# DualPanningMixer.net
KiCad netlist of a schematic drawn in EAGLE
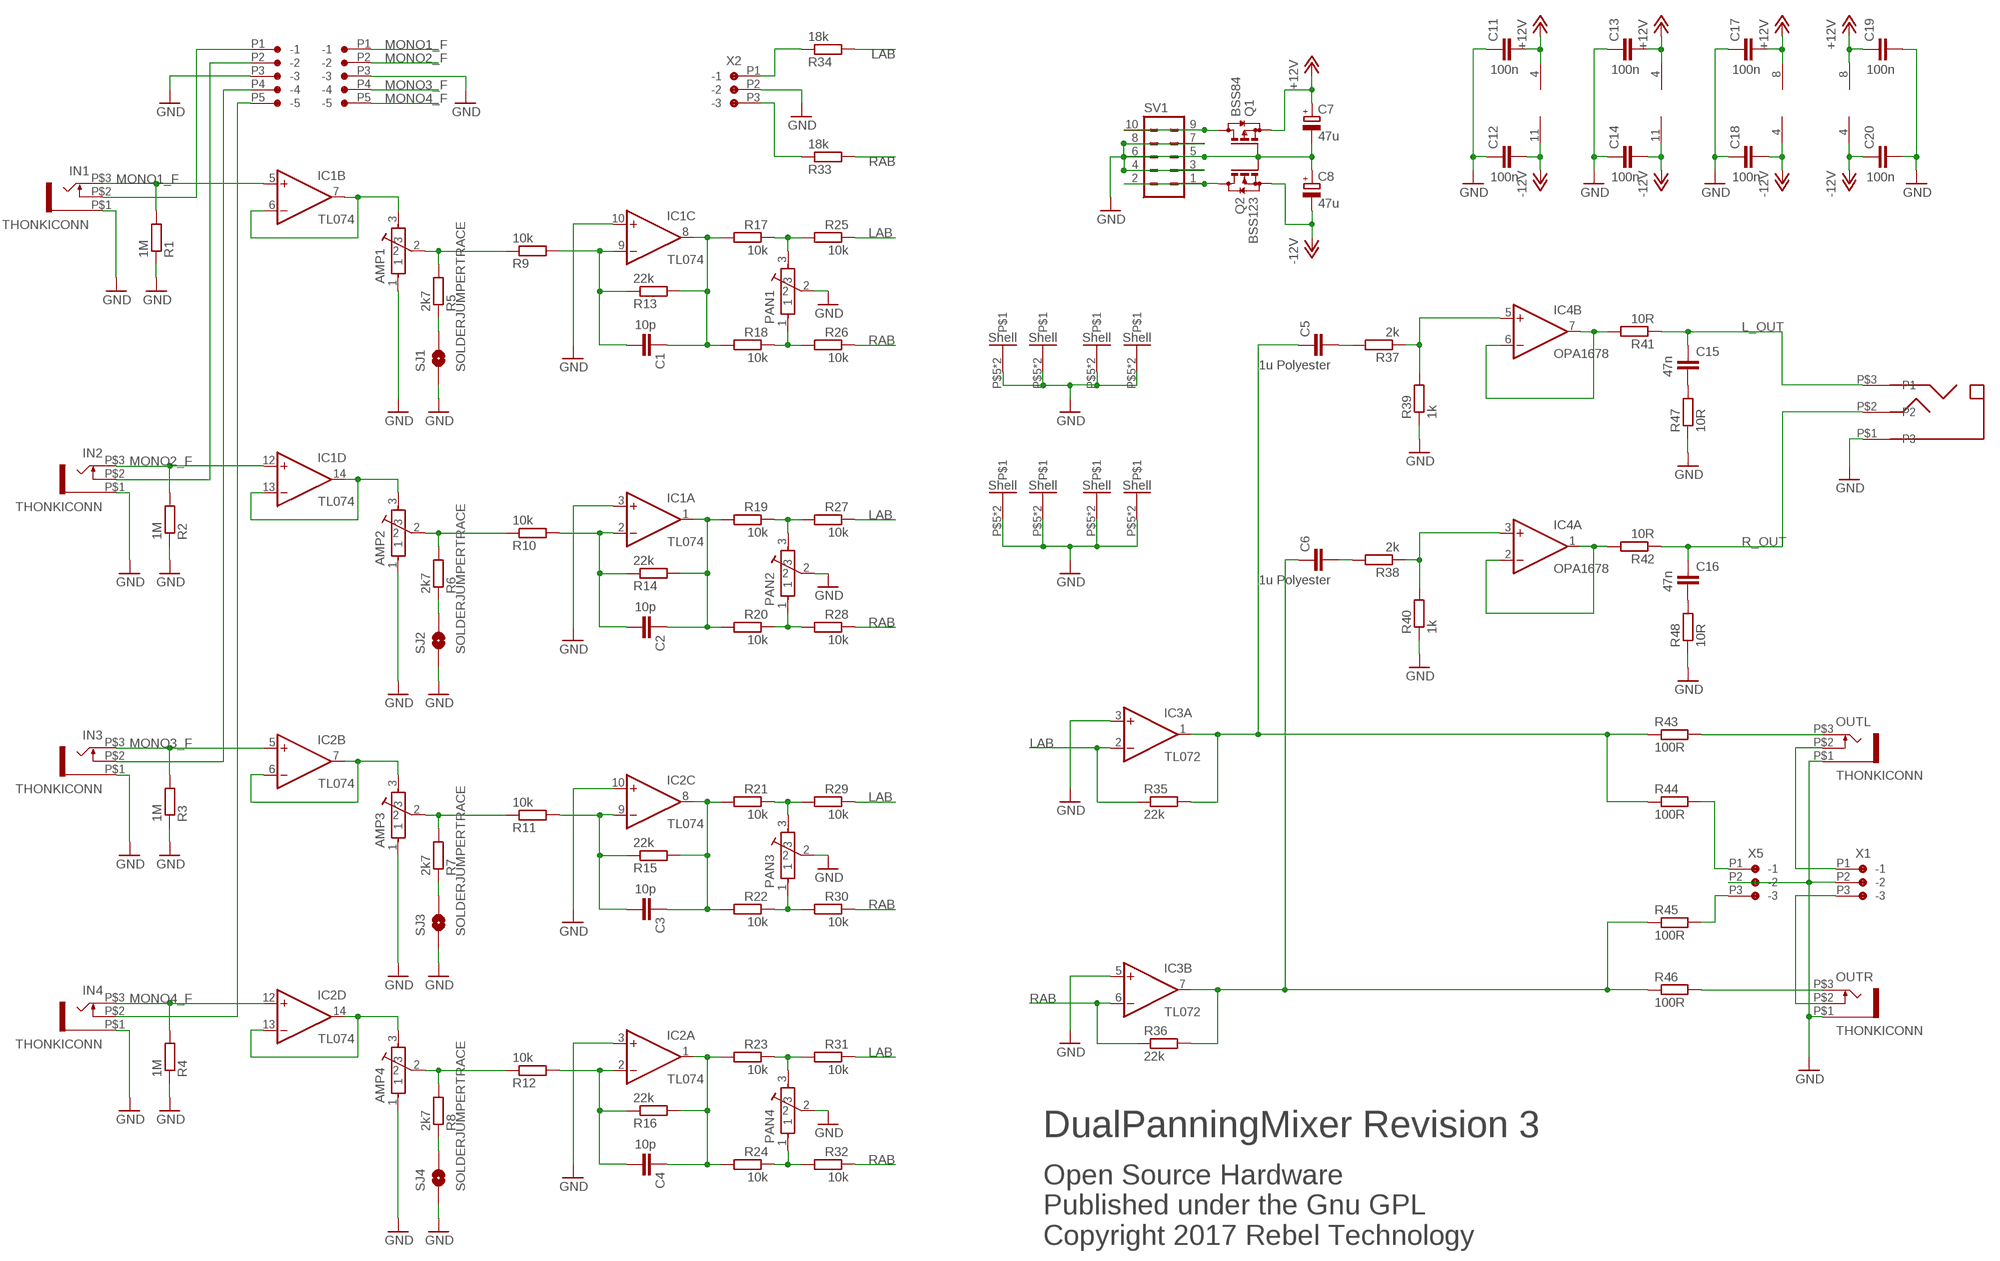
[diagram p0: schematic, sheet 1]

(export (version "E")
  (design (tool "Eeschema 10.0.6"))
  (components
    (comp (ref "AMP1")
      (value "POT-ALPS-RK09L1140")
      (footprint "eagle-import:POT-ALPS-RK09L1140")
      (libsource (lib "eagle-import") (part "POT-ALPS-RK09L1140"))
    )
    (comp (ref "AMP2")
      (value "POT-ALPS-RK09L1140")
      (footprint "eagle-import:POT-ALPS-RK09L1140")
      (libsource (lib "eagle-import") (part "POT-ALPS-RK09L1140"))
    )
    (comp (ref "AMP3")
      (value "POT-ALPS-RK09L1140")
      (footprint "eagle-import:POT-ALPS-RK09L1140")
      (libsource (lib "eagle-import") (part "POT-ALPS-RK09L1140"))
    )
    (comp (ref "AMP4")
      (value "POT-ALPS-RK09L1140")
      (footprint "eagle-import:POT-ALPS-RK09L1140")
      (libsource (lib "eagle-import") (part "POT-ALPS-RK09L1140"))
    )
    (comp (ref "C1")
      (value "10p")
      (footprint "eagle-import:C0603")
      (libsource (lib "eagle-import") (part "C-EUC0603"))
    )
    (comp (ref "C2")
      (value "10p")
      (footprint "eagle-import:C0603")
      (libsource (lib "eagle-import") (part "C-EUC0603"))
    )
    (comp (ref "C3")
      (value "10p")
      (footprint "eagle-import:C0603")
      (libsource (lib "eagle-import") (part "C-EUC0603"))
    )
    (comp (ref "C4")
      (value "10p")
      (footprint "eagle-import:C0603")
      (libsource (lib "eagle-import") (part "C-EUC0603"))
    )
    (comp (ref "C5")
      (value "1u Polyester")
      (footprint "eagle-import:C1210")
      (libsource (lib "eagle-import") (part "C-EUC1210"))
    )
    (comp (ref "C6")
      (value "1u Polyester")
      (footprint "eagle-import:C1210")
      (libsource (lib "eagle-import") (part "C-EUC1210"))
    )
    (comp (ref "C7")
      (value "47u")
      (footprint "eagle-import:UD-5X5,8_NICHICON")
      (libsource (lib "eagle-import") (part "CPOL-EUUD-5X5,8"))
    )
    (comp (ref "C8")
      (value "47u")
      (footprint "eagle-import:UD-5X5,8_NICHICON")
      (libsource (lib "eagle-import") (part "CPOL-EUUD-5X5,8"))
    )
    (comp (ref "C11")
      (value "100n")
      (footprint "eagle-import:C0603")
      (libsource (lib "eagle-import") (part "C-EUC0603"))
    )
    (comp (ref "C12")
      (value "100n")
      (footprint "eagle-import:C0603")
      (libsource (lib "eagle-import") (part "C-EUC0603"))
    )
    (comp (ref "C13")
      (value "100n")
      (footprint "eagle-import:C0603")
      (libsource (lib "eagle-import") (part "C-EUC0603"))
    )
    (comp (ref "C14")
      (value "100n")
      (footprint "eagle-import:C0603")
      (libsource (lib "eagle-import") (part "C-EUC0603"))
    )
    (comp (ref "C15")
      (value "47n")
      (footprint "eagle-import:C0603")
      (libsource (lib "eagle-import") (part "C-EUC0603"))
    )
    (comp (ref "C16")
      (value "47n")
      (footprint "eagle-import:C0603")
      (libsource (lib "eagle-import") (part "C-EUC0603"))
    )
    (comp (ref "C17")
      (value "100n")
      (footprint "eagle-import:C0603")
      (libsource (lib "eagle-import") (part "C-EUC0603"))
    )
    (comp (ref "C18")
      (value "100n")
      (footprint "eagle-import:C0603")
      (libsource (lib "eagle-import") (part "C-EUC0603"))
    )
    (comp (ref "C19")
      (value "100n")
      (footprint "eagle-import:C0603")
      (libsource (lib "eagle-import") (part "C-EUC0603"))
    )
    (comp (ref "C20")
      (value "100n")
      (footprint "eagle-import:C0603")
      (libsource (lib "eagle-import") (part "C-EUC0603"))
    )
    (comp (ref "IC1")
      (value "TL074")
      (footprint "eagle-import:SO14")
      (libsource (lib "eagle-import") (part "TL074D"))
    )
    (comp (ref "IC2")
      (value "TL074")
      (footprint "eagle-import:SO14")
      (libsource (lib "eagle-import") (part "TL074D"))
    )
    (comp (ref "IC3")
      (value "TL072")
      (footprint "eagle-import:SO08")
      (libsource (lib "eagle-import") (part "NE5532D"))
    )
    (comp (ref "IC4")
      (value "OPA1678")
      (footprint "eagle-import:SO08")
      (libsource (lib "eagle-import") (part "NE5532D"))
    )
    (comp (ref "IN1")
      (value "THONKICONN")
      (footprint "eagle-import:THONKICONN")
      (libsource (lib "eagle-import") (part "THONKICONN"))
    )
    (comp (ref "IN2")
      (value "THONKICONN")
      (footprint "eagle-import:THONKICONN")
      (libsource (lib "eagle-import") (part "THONKICONN"))
    )
    (comp (ref "IN3")
      (value "THONKICONN")
      (footprint "eagle-import:THONKICONN")
      (libsource (lib "eagle-import") (part "THONKICONN"))
    )
    (comp (ref "IN4")
      (value "THONKICONN")
      (footprint "eagle-import:THONKICONN")
      (libsource (lib "eagle-import") (part "THONKICONN"))
    )
    (comp (ref "OUTHP")
      (value "THONKICONN_STEREO")
      (footprint "eagle-import:THONKICONN_STEREO")
      (libsource (lib "eagle-import") (part "THONKICONN_STEREO"))
    )
    (comp (ref "OUTL")
      (value "THONKICONN")
      (footprint "eagle-import:THONKICONN")
      (libsource (lib "eagle-import") (part "THONKICONN"))
    )
    (comp (ref "OUTR")
      (value "THONKICONN")
      (footprint "eagle-import:THONKICONN")
      (libsource (lib "eagle-import") (part "THONKICONN"))
    )
    (comp (ref "PAN1")
      (value "POT-ALPS-RK09L1140")
      (footprint "eagle-import:POT-ALPS-RK09L1140")
      (libsource (lib "eagle-import") (part "POT-ALPS-RK09L1140"))
    )
    (comp (ref "PAN2")
      (value "POT-ALPS-RK09L1140")
      (footprint "eagle-import:POT-ALPS-RK09L1140")
      (libsource (lib "eagle-import") (part "POT-ALPS-RK09L1140"))
    )
    (comp (ref "PAN3")
      (value "POT-ALPS-RK09L1140")
      (footprint "eagle-import:POT-ALPS-RK09L1140")
      (libsource (lib "eagle-import") (part "POT-ALPS-RK09L1140"))
    )
    (comp (ref "PAN4")
      (value "POT-ALPS-RK09L1140")
      (footprint "eagle-import:POT-ALPS-RK09L1140")
      (libsource (lib "eagle-import") (part "POT-ALPS-RK09L1140"))
    )
    (comp (ref "Q1")
      (value "BSS84")
      (footprint "eagle-import:SOT23")
      (libsource (lib "eagle-import") (part "BSS84"))
    )
    (comp (ref "Q2")
      (value "BSS123")
      (footprint "eagle-import:SOT23")
      (libsource (lib "eagle-import") (part "BSS123"))
    )
    (comp (ref "R1")
      (value "1M")
      (footprint "eagle-import:0603")
      (libsource (lib "eagle-import") (part "R-EU_0603"))
    )
    (comp (ref "R2")
      (value "1M")
      (footprint "eagle-import:0603")
      (libsource (lib "eagle-import") (part "R-EU_0603"))
    )
    (comp (ref "R3")
      (value "1M")
      (footprint "eagle-import:0603")
      (libsource (lib "eagle-import") (part "R-EU_0603"))
    )
    (comp (ref "R4")
      (value "1M")
      (footprint "eagle-import:0603")
      (libsource (lib "eagle-import") (part "R-EU_0603"))
    )
    (comp (ref "R5")
      (value "2k7")
      (footprint "eagle-import:0603")
      (libsource (lib "eagle-import") (part "R-EU_0603"))
    )
    (comp (ref "R6")
      (value "2k7")
      (footprint "eagle-import:0603")
      (libsource (lib "eagle-import") (part "R-EU_0603"))
    )
    (comp (ref "R7")
      (value "2k7")
      (footprint "eagle-import:0603")
      (libsource (lib "eagle-import") (part "R-EU_0603"))
    )
    (comp (ref "R8")
      (value "2k7")
      (footprint "eagle-import:0603")
      (libsource (lib "eagle-import") (part "R-EU_0603"))
    )
    (comp (ref "R9")
      (value "10k")
      (footprint "eagle-import:0603")
      (libsource (lib "eagle-import") (part "R-EU_0603"))
    )
    (comp (ref "R10")
      (value "10k")
      (footprint "eagle-import:0603")
      (libsource (lib "eagle-import") (part "R-EU_0603"))
    )
    (comp (ref "R11")
      (value "10k")
      (footprint "eagle-import:0603")
      (libsource (lib "eagle-import") (part "R-EU_0603"))
    )
    (comp (ref "R12")
      (value "10k")
      (footprint "eagle-import:0603")
      (libsource (lib "eagle-import") (part "R-EU_0603"))
    )
    (comp (ref "R13")
      (value "22k")
      (footprint "eagle-import:0603")
      (libsource (lib "eagle-import") (part "R-EU_0603"))
    )
    (comp (ref "R14")
      (value "22k")
      (footprint "eagle-import:0603")
      (libsource (lib "eagle-import") (part "R-EU_0603"))
    )
    (comp (ref "R15")
      (value "22k")
      (footprint "eagle-import:0603")
      (libsource (lib "eagle-import") (part "R-EU_0603"))
    )
    (comp (ref "R16")
      (value "22k")
      (footprint "eagle-import:0603")
      (libsource (lib "eagle-import") (part "R-EU_0603"))
    )
    (comp (ref "R17")
      (value "10k")
      (footprint "eagle-import:0603")
      (libsource (lib "eagle-import") (part "R-EU_0603"))
    )
    (comp (ref "R18")
      (value "10k")
      (footprint "eagle-import:0603")
      (libsource (lib "eagle-import") (part "R-EU_0603"))
    )
    (comp (ref "R19")
      (value "10k")
      (footprint "eagle-import:0603")
      (libsource (lib "eagle-import") (part "R-EU_0603"))
    )
    (comp (ref "R20")
      (value "10k")
      (footprint "eagle-import:0603")
      (libsource (lib "eagle-import") (part "R-EU_0603"))
    )
    (comp (ref "R21")
      (value "10k")
      (footprint "eagle-import:0603")
      (libsource (lib "eagle-import") (part "R-EU_0603"))
    )
    (comp (ref "R22")
      (value "10k")
      (footprint "eagle-import:0603")
      (libsource (lib "eagle-import") (part "R-EU_0603"))
    )
    (comp (ref "R23")
      (value "10k")
      (footprint "eagle-import:0603")
      (libsource (lib "eagle-import") (part "R-EU_0603"))
    )
    (comp (ref "R24")
      (value "10k")
      (footprint "eagle-import:0603")
      (libsource (lib "eagle-import") (part "R-EU_0603"))
    )
    (comp (ref "R25")
      (value "10k")
      (footprint "eagle-import:0603")
      (libsource (lib "eagle-import") (part "R-EU_0603"))
    )
    (comp (ref "R26")
      (value "10k")
      (footprint "eagle-import:0603")
      (libsource (lib "eagle-import") (part "R-EU_0603"))
    )
    (comp (ref "R27")
      (value "10k")
      (footprint "eagle-import:0603")
      (libsource (lib "eagle-import") (part "R-EU_0603"))
    )
    (comp (ref "R28")
      (value "10k")
      (footprint "eagle-import:0603")
      (libsource (lib "eagle-import") (part "R-EU_0603"))
    )
    (comp (ref "R29")
      (value "10k")
      (footprint "eagle-import:0603")
      (libsource (lib "eagle-import") (part "R-EU_0603"))
    )
    (comp (ref "R30")
      (value "10k")
      (footprint "eagle-import:0603")
      (libsource (lib "eagle-import") (part "R-EU_0603"))
    )
    (comp (ref "R31")
      (value "10k")
      (footprint "eagle-import:0603")
      (libsource (lib "eagle-import") (part "R-EU_0603"))
    )
    (comp (ref "R32")
      (value "10k")
      (footprint "eagle-import:0603")
      (libsource (lib "eagle-import") (part "R-EU_0603"))
    )
    (comp (ref "R33")
      (value "18k")
      (footprint "eagle-import:0603")
      (libsource (lib "eagle-import") (part "R-EU_0603"))
    )
    (comp (ref "R34")
      (value "18k")
      (footprint "eagle-import:0603")
      (libsource (lib "eagle-import") (part "R-EU_0603"))
    )
    (comp (ref "R35")
      (value "22k")
      (footprint "eagle-import:0603")
      (libsource (lib "eagle-import") (part "R-EU_0603"))
    )
    (comp (ref "R36")
      (value "22k")
      (footprint "eagle-import:0603")
      (libsource (lib "eagle-import") (part "R-EU_0603"))
    )
    (comp (ref "R37")
      (value "2k")
      (footprint "eagle-import:0603")
      (libsource (lib "eagle-import") (part "R-EU_0603"))
    )
    (comp (ref "R38")
      (value "2k")
      (footprint "eagle-import:0603")
      (libsource (lib "eagle-import") (part "R-EU_0603"))
    )
    (comp (ref "R39")
      (value "1k")
      (footprint "eagle-import:0603")
      (libsource (lib "eagle-import") (part "R-EU_0603"))
    )
    (comp (ref "R40")
      (value "1k")
      (footprint "eagle-import:0603")
      (libsource (lib "eagle-import") (part "R-EU_0603"))
    )
    (comp (ref "R41")
      (value "10R")
      (footprint "eagle-import:0603")
      (libsource (lib "eagle-import") (part "R-EU_0603"))
    )
    (comp (ref "R42")
      (value "10R")
      (footprint "eagle-import:0603")
      (libsource (lib "eagle-import") (part "R-EU_0603"))
    )
    (comp (ref "R43")
      (value "100R")
      (footprint "eagle-import:0603")
      (libsource (lib "eagle-import") (part "R-EU_0603"))
    )
    (comp (ref "R44")
      (value "100R")
      (footprint "eagle-import:0603")
      (libsource (lib "eagle-import") (part "R-EU_0603"))
    )
    (comp (ref "R45")
      (value "100R")
      (footprint "eagle-import:0603")
      (libsource (lib "eagle-import") (part "R-EU_0603"))
    )
    (comp (ref "R46")
      (value "100R")
      (footprint "eagle-import:0603")
      (libsource (lib "eagle-import") (part "R-EU_0603"))
    )
    (comp (ref "R47")
      (value "10R")
      (footprint "eagle-import:0603")
      (libsource (lib "eagle-import") (part "R-EU_0603"))
    )
    (comp (ref "R48")
      (value "10R")
      (footprint "eagle-import:0603")
      (libsource (lib "eagle-import") (part "R-EU_0603"))
    )
    (comp (ref "SJ1")
      (value "SOLDERJUMPERTRACE")
      (footprint "eagle-import:SJ_2S-TRACE")
      (libsource (lib "eagle-import") (part "SOLDERJUMPERTRACE"))
    )
    (comp (ref "SJ2")
      (value "SOLDERJUMPERTRACE")
      (footprint "eagle-import:SJ_2S-TRACE")
      (libsource (lib "eagle-import") (part "SOLDERJUMPERTRACE"))
    )
    (comp (ref "SJ3")
      (value "SOLDERJUMPERTRACE")
      (footprint "eagle-import:SJ_2S-TRACE")
      (libsource (lib "eagle-import") (part "SOLDERJUMPERTRACE"))
    )
    (comp (ref "SJ4")
      (value "SOLDERJUMPERTRACE")
      (footprint "eagle-import:SJ_2S-TRACE")
      (libsource (lib "eagle-import") (part "SOLDERJUMPERTRACE"))
    )
    (comp (ref "SV1")
      (value "MA05-2")
      (footprint "eagle-import:MA05-2")
      (libsource (lib "eagle-import") (part "MA05-2"))
    )
    (comp (ref "X1")
      (value "CON-JST_PH_3W")
      (footprint "eagle-import:CON-JST_PH_3W")
      (libsource (lib "eagle-import") (part "CON-JST_PH_3W"))
    )
    (comp (ref "X2")
      (value "CON-JST_PH_3W")
      (footprint "eagle-import:CON-JST_PH_3W")
      (libsource (lib "eagle-import") (part "CON-JST_PH_3W"))
    )
    (comp (ref "X3")
      (value "CON-JST_PH_5W")
      (footprint "eagle-import:CON-JST_PH_5W")
      (libsource (lib "eagle-import") (part "CON-JST_PH_5W"))
    )
    (comp (ref "X4")
      (value "CON-JST_PH_5W")
      (footprint "eagle-import:CON-JST_PH_5W")
      (libsource (lib "eagle-import") (part "CON-JST_PH_5W"))
    )
    (comp (ref "X5")
      (value "CON-JST_PH_3W")
      (footprint "eagle-import:CON-JST_PH_3W")
      (libsource (lib "eagle-import") (part "CON-JST_PH_3W"))
    )
  )
  (nets
    (net (code "1") (name "+12V") (class "Default")
      (node (ref "C11") (pin "2") (pinfunction "2_2") (pintype "passive"))
      (node (ref "C13") (pin "2") (pinfunction "2_2") (pintype "passive"))
      (node (ref "C17") (pin "2") (pinfunction "2_2") (pintype "passive"))
      (node (ref "C19") (pin "1") (pinfunction "1_1") (pintype "passive"))
      (node (ref "C7") (pin "+") (pinfunction "+_+") (pintype "passive"))
      (node (ref "IC1") (pin "4") (pinfunction "V+_4") (pintype "power_in"))
      (node (ref "IC2") (pin "4") (pinfunction "V+_4") (pintype "power_in"))
      (node (ref "IC3") (pin "8") (pinfunction "V+_8") (pintype "power_in"))
      (node (ref "IC4") (pin "8") (pinfunction "V+_8") (pintype "power_in"))
      (node (ref "Q1") (pin "2") (pinfunction "S_2") (pintype "passive"))
    )
    (net (code "2") (name "-12V") (class "Default")
      (node (ref "C12") (pin "2") (pinfunction "2_2") (pintype "passive"))
      (node (ref "C14") (pin "2") (pinfunction "2_2") (pintype "passive"))
      (node (ref "C18") (pin "2") (pinfunction "2_2") (pintype "passive"))
      (node (ref "C20") (pin "1") (pinfunction "1_1") (pintype "passive"))
      (node (ref "C8") (pin "-") (pinfunction "-_-") (pintype "passive"))
      (node (ref "IC1") (pin "11") (pinfunction "V-_11") (pintype "power_in"))
      (node (ref "IC2") (pin "11") (pinfunction "V-_11") (pintype "power_in"))
      (node (ref "IC3") (pin "4") (pinfunction "V-_4") (pintype "power_in"))
      (node (ref "IC4") (pin "4") (pinfunction "V-_4") (pintype "power_in"))
      (node (ref "Q2") (pin "2") (pinfunction "S_2") (pintype "passive"))
    )
    (net (code "3") (name "/LAB") (class "Default")
      (node (ref "IC3") (pin "2") (pinfunction "-IN_2") (pintype "input"))
      (node (ref "R25") (pin "1") (pinfunction "1_1") (pintype "passive"))
      (node (ref "R27") (pin "1") (pinfunction "1_1") (pintype "passive"))
      (node (ref "R29") (pin "1") (pinfunction "1_1") (pintype "passive"))
      (node (ref "R31") (pin "1") (pinfunction "1_1") (pintype "passive"))
      (node (ref "R34") (pin "2") (pinfunction "2_2") (pintype "passive"))
      (node (ref "R35") (pin "1") (pinfunction "1_1") (pintype "passive"))
    )
    (net (code "4") (name "/L_OUT") (class "Default")
      (node (ref "C15") (pin "1") (pinfunction "1_1") (pintype "passive"))
      (node (ref "OUTHP") (pin "P$3") (pinfunction "P1_P$3") (pintype "bidirectional"))
      (node (ref "R41") (pin "1") (pinfunction "1_1") (pintype "passive"))
    )
    (net (code "5") (name "/MONO1_F") (class "Default")
      (node (ref "IC1") (pin "5") (pinfunction "+IN_5") (pintype "input"))
      (node (ref "IN1") (pin "P$3") (pinfunction "3_P$3") (pintype "passive"))
      (node (ref "R1") (pin "2") (pinfunction "2_2") (pintype "passive"))
      (node (ref "X3") (pin "P1") (pinfunction "-1_P1") (pintype "bidirectional"))
    )
    (net (code "6") (name "/MONO2_F") (class "Default")
      (node (ref "IC1") (pin "12") (pinfunction "+IN_12") (pintype "input"))
      (node (ref "IN2") (pin "P$3") (pinfunction "3_P$3") (pintype "passive"))
      (node (ref "R2") (pin "2") (pinfunction "2_2") (pintype "passive"))
      (node (ref "X3") (pin "P2") (pinfunction "-2_P2") (pintype "bidirectional"))
    )
    (net (code "7") (name "/MONO3_F") (class "Default")
      (node (ref "IC2") (pin "5") (pinfunction "+IN_5") (pintype "input"))
      (node (ref "IN3") (pin "P$3") (pinfunction "3_P$3") (pintype "passive"))
      (node (ref "R3") (pin "2") (pinfunction "2_2") (pintype "passive"))
      (node (ref "X3") (pin "P4") (pinfunction "-4_P4") (pintype "bidirectional"))
    )
    (net (code "8") (name "/MONO4_F") (class "Default")
      (node (ref "IC2") (pin "12") (pinfunction "+IN_12") (pintype "input"))
      (node (ref "IN4") (pin "P$3") (pinfunction "3_P$3") (pintype "passive"))
      (node (ref "R4") (pin "2") (pinfunction "2_2") (pintype "passive"))
      (node (ref "X3") (pin "P5") (pinfunction "-5_P5") (pintype "bidirectional"))
    )
    (net (code "9") (name "/RAB") (class "Default")
      (node (ref "IC3") (pin "6") (pinfunction "-IN_6") (pintype "input"))
      (node (ref "R26") (pin "1") (pinfunction "1_1") (pintype "passive"))
      (node (ref "R28") (pin "1") (pinfunction "1_1") (pintype "passive"))
      (node (ref "R30") (pin "1") (pinfunction "1_1") (pintype "passive"))
      (node (ref "R32") (pin "1") (pinfunction "1_1") (pintype "passive"))
      (node (ref "R33") (pin "2") (pinfunction "2_2") (pintype "passive"))
      (node (ref "R36") (pin "1") (pinfunction "1_1") (pintype "passive"))
    )
    (net (code "10") (name "/R_OUT") (class "Default")
      (node (ref "C16") (pin "1") (pinfunction "1_1") (pintype "passive"))
      (node (ref "OUTHP") (pin "P$2") (pinfunction "P2_P$2") (pintype "bidirectional"))
      (node (ref "R42") (pin "1") (pinfunction "1_1") (pintype "passive"))
    )
    (net (code "11") (name "GND") (class "Default")
      (node (ref "AMP1") (pin "1") (pinfunction "1_1") (pintype "bidirectional"))
      (node (ref "AMP1") (pin "P$5") (pinfunction "P$1_P$5") (pintype "bidirectional"))
      (node (ref "AMP1") (pin "P$6") (pinfunction "P$1_P$6") (pintype "bidirectional"))
      (node (ref "AMP2") (pin "1") (pinfunction "1_1") (pintype "bidirectional"))
      (node (ref "AMP2") (pin "P$5") (pinfunction "P$1_P$5") (pintype "bidirectional"))
      (node (ref "AMP2") (pin "P$6") (pinfunction "P$1_P$6") (pintype "bidirectional"))
      (node (ref "AMP3") (pin "1") (pinfunction "1_1") (pintype "bidirectional"))
      (node (ref "AMP3") (pin "P$5") (pinfunction "P$1_P$5") (pintype "bidirectional"))
      (node (ref "AMP3") (pin "P$6") (pinfunction "P$1_P$6") (pintype "bidirectional"))
      (node (ref "AMP4") (pin "1") (pinfunction "1_1") (pintype "bidirectional"))
      (node (ref "AMP4") (pin "P$5") (pinfunction "P$1_P$5") (pintype "bidirectional"))
      (node (ref "AMP4") (pin "P$6") (pinfunction "P$1_P$6") (pintype "bidirectional"))
      (node (ref "C11") (pin "1") (pinfunction "1_1") (pintype "passive"))
      (node (ref "C12") (pin "1") (pinfunction "1_1") (pintype "passive"))
      (node (ref "C13") (pin "1") (pinfunction "1_1") (pintype "passive"))
      (node (ref "C14") (pin "1") (pinfunction "1_1") (pintype "passive"))
      (node (ref "C17") (pin "1") (pinfunction "1_1") (pintype "passive"))
      (node (ref "C18") (pin "1") (pinfunction "1_1") (pintype "passive"))
      (node (ref "C19") (pin "2") (pinfunction "2_2") (pintype "passive"))
      (node (ref "C20") (pin "2") (pinfunction "2_2") (pintype "passive"))
      (node (ref "C7") (pin "-") (pinfunction "-_-") (pintype "passive"))
      (node (ref "C8") (pin "+") (pinfunction "+_+") (pintype "passive"))
      (node (ref "IC1") (pin "10") (pinfunction "+IN_10") (pintype "input"))
      (node (ref "IC1") (pin "3") (pinfunction "+IN_3") (pintype "input"))
      (node (ref "IC2") (pin "10") (pinfunction "+IN_10") (pintype "input"))
      (node (ref "IC2") (pin "3") (pinfunction "+IN_3") (pintype "input"))
      (node (ref "IC3") (pin "3") (pinfunction "+IN_3") (pintype "input"))
      (node (ref "IC3") (pin "5") (pinfunction "+IN_5") (pintype "input"))
      (node (ref "IN1") (pin "P$1") (pinfunction "5_P$1") (pintype "passive"))
      (node (ref "IN2") (pin "P$1") (pinfunction "5_P$1") (pintype "passive"))
      (node (ref "IN3") (pin "P$1") (pinfunction "5_P$1") (pintype "passive"))
      (node (ref "IN4") (pin "P$1") (pinfunction "5_P$1") (pintype "passive"))
      (node (ref "OUTHP") (pin "P$1") (pinfunction "P3_P$1") (pintype "bidirectional"))
      (node (ref "OUTL") (pin "P$1") (pinfunction "5_P$1") (pintype "passive"))
      (node (ref "OUTR") (pin "P$1") (pinfunction "5_P$1") (pintype "passive"))
      (node (ref "PAN1") (pin "2") (pinfunction "2_2") (pintype "bidirectional"))
      (node (ref "PAN1") (pin "P$5") (pinfunction "P$1_P$5") (pintype "bidirectional"))
      (node (ref "PAN1") (pin "P$6") (pinfunction "P$1_P$6") (pintype "bidirectional"))
      (node (ref "PAN2") (pin "2") (pinfunction "2_2") (pintype "bidirectional"))
      (node (ref "PAN2") (pin "P$5") (pinfunction "P$1_P$5") (pintype "bidirectional"))
      (node (ref "PAN2") (pin "P$6") (pinfunction "P$1_P$6") (pintype "bidirectional"))
      (node (ref "PAN3") (pin "2") (pinfunction "2_2") (pintype "bidirectional"))
      (node (ref "PAN3") (pin "P$5") (pinfunction "P$1_P$5") (pintype "bidirectional"))
      (node (ref "PAN3") (pin "P$6") (pinfunction "P$1_P$6") (pintype "bidirectional"))
      (node (ref "PAN4") (pin "2") (pinfunction "2_2") (pintype "bidirectional"))
      (node (ref "PAN4") (pin "P$5") (pinfunction "P$1_P$5") (pintype "bidirectional"))
      (node (ref "PAN4") (pin "P$6") (pinfunction "P$1_P$6") (pintype "bidirectional"))
      (node (ref "Q1") (pin "1") (pinfunction "G_1") (pintype "passive"))
      (node (ref "Q2") (pin "1") (pinfunction "G_1") (pintype "passive"))
      (node (ref "R1") (pin "1") (pinfunction "1_1") (pintype "passive"))
      (node (ref "R2") (pin "1") (pinfunction "1_1") (pintype "passive"))
      (node (ref "R3") (pin "1") (pinfunction "1_1") (pintype "passive"))
      (node (ref "R39") (pin "1") (pinfunction "1_1") (pintype "passive"))
      (node (ref "R4") (pin "1") (pinfunction "1_1") (pintype "passive"))
      (node (ref "R40") (pin "1") (pinfunction "1_1") (pintype "passive"))
      (node (ref "R47") (pin "1") (pinfunction "1_1") (pintype "passive"))
      (node (ref "R48") (pin "1") (pinfunction "1_1") (pintype "passive"))
      (node (ref "SJ1") (pin "1") (pinfunction "1_1") (pintype "passive"))
      (node (ref "SJ2") (pin "1") (pinfunction "1_1") (pintype "passive"))
      (node (ref "SJ3") (pin "1") (pinfunction "1_1") (pintype "passive"))
      (node (ref "SJ4") (pin "1") (pinfunction "1_1") (pintype "passive"))
      (node (ref "SV1") (pin "3") (pinfunction "3_3") (pintype "passive"))
      (node (ref "SV1") (pin "4") (pinfunction "4_4") (pintype "passive"))
      (node (ref "SV1") (pin "5") (pinfunction "5_5") (pintype "passive"))
      (node (ref "SV1") (pin "6") (pinfunction "6_6") (pintype "passive"))
      (node (ref "SV1") (pin "7") (pinfunction "7_7") (pintype "passive"))
      (node (ref "SV1") (pin "8") (pinfunction "8_8") (pintype "passive"))
      (node (ref "X1") (pin "P2") (pinfunction "-2_P2") (pintype "bidirectional"))
      (node (ref "X2") (pin "P2") (pinfunction "-2_P2") (pintype "bidirectional"))
      (node (ref "X3") (pin "P3") (pinfunction "-3_P3") (pintype "bidirectional"))
      (node (ref "X4") (pin "P3") (pinfunction "-3_P3") (pintype "bidirectional"))
      (node (ref "X5") (pin "P2") (pinfunction "-2_P2") (pintype "bidirectional"))
    )
    (net (code "12") (name "Net-(AMP1-Pad2)") (class "Default")
      (node (ref "AMP1") (pin "2") (pinfunction "2_2") (pintype "bidirectional"))
      (node (ref "R5") (pin "2") (pinfunction "2_2") (pintype "passive"))
      (node (ref "R9") (pin "1") (pinfunction "1_1") (pintype "passive"))
    )
    (net (code "13") (name "Net-(AMP2-Pad2)") (class "Default")
      (node (ref "AMP2") (pin "2") (pinfunction "2_2") (pintype "bidirectional"))
      (node (ref "R10") (pin "1") (pinfunction "1_1") (pintype "passive"))
      (node (ref "R6") (pin "2") (pinfunction "2_2") (pintype "passive"))
    )
    (net (code "14") (name "Net-(AMP3-Pad2)") (class "Default")
      (node (ref "AMP3") (pin "2") (pinfunction "2_2") (pintype "bidirectional"))
      (node (ref "R11") (pin "1") (pinfunction "1_1") (pintype "passive"))
      (node (ref "R7") (pin "2") (pinfunction "2_2") (pintype "passive"))
    )
    (net (code "15") (name "Net-(AMP4-Pad2)") (class "Default")
      (node (ref "AMP4") (pin "2") (pinfunction "2_2") (pintype "bidirectional"))
      (node (ref "R12") (pin "1") (pinfunction "1_1") (pintype "passive"))
      (node (ref "R8") (pin "2") (pinfunction "2_2") (pintype "passive"))
    )
    (net (code "16") (name "Net-(C5-Pad2)") (class "Default")
      (node (ref "C5") (pin "2") (pinfunction "2_2") (pintype "passive"))
      (node (ref "R37") (pin "2") (pinfunction "2_2") (pintype "passive"))
    )
    (net (code "17") (name "Net-(C6-Pad2)") (class "Default")
      (node (ref "C6") (pin "2") (pinfunction "2_2") (pintype "passive"))
      (node (ref "R38") (pin "2") (pinfunction "2_2") (pintype "passive"))
    )
    (net (code "18") (name "Net-(C15-Pad2)") (class "Default")
      (node (ref "C15") (pin "2") (pinfunction "2_2") (pintype "passive"))
      (node (ref "R47") (pin "2") (pinfunction "2_2") (pintype "passive"))
    )
    (net (code "19") (name "Net-(C16-Pad2)") (class "Default")
      (node (ref "C16") (pin "2") (pinfunction "2_2") (pintype "passive"))
      (node (ref "R48") (pin "2") (pinfunction "2_2") (pintype "passive"))
    )
    (net (code "20") (name "Net-(IC1A--IN)") (class "Default")
      (node (ref "C2") (pin "2") (pinfunction "2_2") (pintype "passive"))
      (node (ref "IC1") (pin "2") (pinfunction "-IN_2") (pintype "input"))
      (node (ref "R10") (pin "2") (pinfunction "2_2") (pintype "passive"))
      (node (ref "R14") (pin "1") (pinfunction "1_1") (pintype "passive"))
    )
    (net (code "21") (name "Net-(IC1A-OUT)") (class "Default")
      (node (ref "C2") (pin "1") (pinfunction "1_1") (pintype "passive"))
      (node (ref "IC1") (pin "1") (pinfunction "OUT_1") (pintype "output"))
      (node (ref "R14") (pin "2") (pinfunction "2_2") (pintype "passive"))
      (node (ref "R19") (pin "2") (pinfunction "2_2") (pintype "passive"))
      (node (ref "R20") (pin "2") (pinfunction "2_2") (pintype "passive"))
    )
    (net (code "22") (name "Net-(IC1B--IN)") (class "Default")
      (node (ref "AMP1") (pin "3") (pinfunction "3_3") (pintype "bidirectional"))
      (node (ref "IC1") (pin "6") (pinfunction "-IN_6") (pintype "input"))
      (node (ref "IC1") (pin "7") (pinfunction "OUT_7") (pintype "output"))
    )
    (net (code "23") (name "Net-(IC1C--IN)") (class "Default")
      (node (ref "C1") (pin "2") (pinfunction "2_2") (pintype "passive"))
      (node (ref "IC1") (pin "9") (pinfunction "-IN_9") (pintype "input"))
      (node (ref "R13") (pin "1") (pinfunction "1_1") (pintype "passive"))
      (node (ref "R9") (pin "2") (pinfunction "2_2") (pintype "passive"))
    )
    (net (code "24") (name "Net-(IC1C-OUT)") (class "Default")
      (node (ref "C1") (pin "1") (pinfunction "1_1") (pintype "passive"))
      (node (ref "IC1") (pin "8") (pinfunction "OUT_8") (pintype "output"))
      (node (ref "R13") (pin "2") (pinfunction "2_2") (pintype "passive"))
      (node (ref "R17") (pin "2") (pinfunction "2_2") (pintype "passive"))
      (node (ref "R18") (pin "2") (pinfunction "2_2") (pintype "passive"))
    )
    (net (code "25") (name "Net-(IC1D--IN)") (class "Default")
      (node (ref "AMP2") (pin "3") (pinfunction "3_3") (pintype "bidirectional"))
      (node (ref "IC1") (pin "13") (pinfunction "-IN_13") (pintype "input"))
      (node (ref "IC1") (pin "14") (pinfunction "OUT_14") (pintype "output"))
    )
    (net (code "26") (name "Net-(IC2A--IN)") (class "Default")
      (node (ref "C4") (pin "2") (pinfunction "2_2") (pintype "passive"))
      (node (ref "IC2") (pin "2") (pinfunction "-IN_2") (pintype "input"))
      (node (ref "R12") (pin "2") (pinfunction "2_2") (pintype "passive"))
      (node (ref "R16") (pin "1") (pinfunction "1_1") (pintype "passive"))
    )
    (net (code "27") (name "Net-(IC2A-OUT)") (class "Default")
      (node (ref "C4") (pin "1") (pinfunction "1_1") (pintype "passive"))
      (node (ref "IC2") (pin "1") (pinfunction "OUT_1") (pintype "output"))
      (node (ref "R16") (pin "2") (pinfunction "2_2") (pintype "passive"))
      (node (ref "R23") (pin "2") (pinfunction "2_2") (pintype "passive"))
      (node (ref "R24") (pin "2") (pinfunction "2_2") (pintype "passive"))
    )
    (net (code "28") (name "Net-(IC2B--IN)") (class "Default")
      (node (ref "AMP3") (pin "3") (pinfunction "3_3") (pintype "bidirectional"))
      (node (ref "IC2") (pin "6") (pinfunction "-IN_6") (pintype "input"))
      (node (ref "IC2") (pin "7") (pinfunction "OUT_7") (pintype "output"))
    )
    (net (code "29") (name "Net-(IC2C--IN)") (class "Default")
      (node (ref "C3") (pin "2") (pinfunction "2_2") (pintype "passive"))
      (node (ref "IC2") (pin "9") (pinfunction "-IN_9") (pintype "input"))
      (node (ref "R11") (pin "2") (pinfunction "2_2") (pintype "passive"))
      (node (ref "R15") (pin "1") (pinfunction "1_1") (pintype "passive"))
    )
    (net (code "30") (name "Net-(IC2C-OUT)") (class "Default")
      (node (ref "C3") (pin "1") (pinfunction "1_1") (pintype "passive"))
      (node (ref "IC2") (pin "8") (pinfunction "OUT_8") (pintype "output"))
      (node (ref "R15") (pin "2") (pinfunction "2_2") (pintype "passive"))
      (node (ref "R21") (pin "2") (pinfunction "2_2") (pintype "passive"))
      (node (ref "R22") (pin "2") (pinfunction "2_2") (pintype "passive"))
    )
    (net (code "31") (name "Net-(IC2D--IN)") (class "Default")
      (node (ref "AMP4") (pin "3") (pinfunction "3_3") (pintype "bidirectional"))
      (node (ref "IC2") (pin "13") (pinfunction "-IN_13") (pintype "input"))
      (node (ref "IC2") (pin "14") (pinfunction "OUT_14") (pintype "output"))
    )
    (net (code "32") (name "Net-(IC3A-OUT)") (class "Default")
      (node (ref "C5") (pin "1") (pinfunction "1_1") (pintype "passive"))
      (node (ref "IC3") (pin "1") (pinfunction "OUT_1") (pintype "output"))
      (node (ref "R35") (pin "2") (pinfunction "2_2") (pintype "passive"))
      (node (ref "R43") (pin "1") (pinfunction "1_1") (pintype "passive"))
      (node (ref "R44") (pin "1") (pinfunction "1_1") (pintype "passive"))
    )
    (net (code "33") (name "Net-(IC3B-OUT)") (class "Default")
      (node (ref "C6") (pin "1") (pinfunction "1_1") (pintype "passive"))
      (node (ref "IC3") (pin "7") (pinfunction "OUT_7") (pintype "output"))
      (node (ref "R36") (pin "2") (pinfunction "2_2") (pintype "passive"))
      (node (ref "R45") (pin "1") (pinfunction "1_1") (pintype "passive"))
      (node (ref "R46") (pin "1") (pinfunction "1_1") (pintype "passive"))
    )
    (net (code "34") (name "Net-(IC4A-+IN)") (class "Default")
      (node (ref "IC4") (pin "3") (pinfunction "+IN_3") (pintype "input"))
      (node (ref "R38") (pin "1") (pinfunction "1_1") (pintype "passive"))
      (node (ref "R40") (pin "2") (pinfunction "2_2") (pintype "passive"))
    )
    (net (code "35") (name "Net-(IC4A--IN)") (class "Default")
      (node (ref "IC4") (pin "1") (pinfunction "OUT_1") (pintype "output"))
      (node (ref "IC4") (pin "2") (pinfunction "-IN_2") (pintype "input"))
      (node (ref "R42") (pin "2") (pinfunction "2_2") (pintype "passive"))
    )
    (net (code "36") (name "Net-(IC4B-+IN)") (class "Default")
      (node (ref "IC4") (pin "5") (pinfunction "+IN_5") (pintype "input"))
      (node (ref "R37") (pin "1") (pinfunction "1_1") (pintype "passive"))
      (node (ref "R39") (pin "2") (pinfunction "2_2") (pintype "passive"))
    )
    (net (code "37") (name "Net-(IC4B--IN)") (class "Default")
      (node (ref "IC4") (pin "6") (pinfunction "-IN_6") (pintype "input"))
      (node (ref "IC4") (pin "7") (pinfunction "OUT_7") (pintype "output"))
      (node (ref "R41") (pin "2") (pinfunction "2_2") (pintype "passive"))
    )
    (net (code "38") (name "Net-(IN1-4)") (class "Default")
      (node (ref "IN1") (pin "P$2") (pinfunction "4_P$2") (pintype "passive"))
      (node (ref "X4") (pin "P1") (pinfunction "-1_P1") (pintype "bidirectional"))
    )
    (net (code "39") (name "Net-(IN2-4)") (class "Default")
      (node (ref "IN2") (pin "P$2") (pinfunction "4_P$2") (pintype "passive"))
      (node (ref "X4") (pin "P2") (pinfunction "-2_P2") (pintype "bidirectional"))
    )
    (net (code "40") (name "Net-(IN3-4)") (class "Default")
      (node (ref "IN3") (pin "P$2") (pinfunction "4_P$2") (pintype "passive"))
      (node (ref "X4") (pin "P4") (pinfunction "-4_P4") (pintype "bidirectional"))
    )
    (net (code "41") (name "Net-(IN4-4)") (class "Default")
      (node (ref "IN4") (pin "P$2") (pinfunction "4_P$2") (pintype "passive"))
      (node (ref "X4") (pin "P5") (pinfunction "-5_P5") (pintype "bidirectional"))
    )
    (net (code "42") (name "Net-(OUTL-3)") (class "Default")
      (node (ref "OUTL") (pin "P$3") (pinfunction "3_P$3") (pintype "passive"))
      (node (ref "R43") (pin "2") (pinfunction "2_2") (pintype "passive"))
    )
    (net (code "43") (name "Net-(OUTL-4)") (class "Default")
      (node (ref "OUTL") (pin "P$2") (pinfunction "4_P$2") (pintype "passive"))
      (node (ref "X1") (pin "P1") (pinfunction "-1_P1") (pintype "bidirectional"))
    )
    (net (code "44") (name "Net-(OUTR-3)") (class "Default")
      (node (ref "OUTR") (pin "P$3") (pinfunction "3_P$3") (pintype "passive"))
      (node (ref "R46") (pin "2") (pinfunction "2_2") (pintype "passive"))
    )
    (net (code "45") (name "Net-(OUTR-4)") (class "Default")
      (node (ref "OUTR") (pin "P$2") (pinfunction "4_P$2") (pintype "passive"))
      (node (ref "X1") (pin "P3") (pinfunction "-3_P3") (pintype "bidirectional"))
    )
    (net (code "46") (name "Net-(PAN1-Pad1)") (class "Default")
      (node (ref "PAN1") (pin "1") (pinfunction "1_1") (pintype "bidirectional"))
      (node (ref "R18") (pin "1") (pinfunction "1_1") (pintype "passive"))
      (node (ref "R26") (pin "2") (pinfunction "2_2") (pintype "passive"))
    )
    (net (code "47") (name "Net-(PAN1-Pad3)") (class "Default")
      (node (ref "PAN1") (pin "3") (pinfunction "3_3") (pintype "bidirectional"))
      (node (ref "R17") (pin "1") (pinfunction "1_1") (pintype "passive"))
      (node (ref "R25") (pin "2") (pinfunction "2_2") (pintype "passive"))
    )
    (net (code "48") (name "Net-(PAN2-Pad1)") (class "Default")
      (node (ref "PAN2") (pin "1") (pinfunction "1_1") (pintype "bidirectional"))
      (node (ref "R20") (pin "1") (pinfunction "1_1") (pintype "passive"))
      (node (ref "R28") (pin "2") (pinfunction "2_2") (pintype "passive"))
    )
    (net (code "49") (name "Net-(PAN2-Pad3)") (class "Default")
      (node (ref "PAN2") (pin "3") (pinfunction "3_3") (pintype "bidirectional"))
      (node (ref "R19") (pin "1") (pinfunction "1_1") (pintype "passive"))
      (node (ref "R27") (pin "2") (pinfunction "2_2") (pintype "passive"))
    )
    (net (code "50") (name "Net-(PAN3-Pad1)") (class "Default")
      (node (ref "PAN3") (pin "1") (pinfunction "1_1") (pintype "bidirectional"))
      (node (ref "R22") (pin "1") (pinfunction "1_1") (pintype "passive"))
      (node (ref "R30") (pin "2") (pinfunction "2_2") (pintype "passive"))
    )
    (net (code "51") (name "Net-(PAN3-Pad3)") (class "Default")
      (node (ref "PAN3") (pin "3") (pinfunction "3_3") (pintype "bidirectional"))
      (node (ref "R21") (pin "1") (pinfunction "1_1") (pintype "passive"))
      (node (ref "R29") (pin "2") (pinfunction "2_2") (pintype "passive"))
    )
    (net (code "52") (name "Net-(PAN4-Pad1)") (class "Default")
      (node (ref "PAN4") (pin "1") (pinfunction "1_1") (pintype "bidirectional"))
      (node (ref "R24") (pin "1") (pinfunction "1_1") (pintype "passive"))
      (node (ref "R32") (pin "2") (pinfunction "2_2") (pintype "passive"))
    )
    (net (code "53") (name "Net-(PAN4-Pad3)") (class "Default")
      (node (ref "PAN4") (pin "3") (pinfunction "3_3") (pintype "bidirectional"))
      (node (ref "R23") (pin "1") (pinfunction "1_1") (pintype "passive"))
      (node (ref "R31") (pin "2") (pinfunction "2_2") (pintype "passive"))
    )
    (net (code "54") (name "Net-(Q1-D)") (class "Default")
      (node (ref "Q1") (pin "3") (pinfunction "D_3") (pintype "passive"))
      (node (ref "SV1") (pin "10") (pinfunction "10_10") (pintype "passive"))
      (node (ref "SV1") (pin "9") (pinfunction "9_9") (pintype "passive"))
    )
    (net (code "55") (name "Net-(Q2-D)") (class "Default")
      (node (ref "Q2") (pin "3") (pinfunction "D_3") (pintype "passive"))
      (node (ref "SV1") (pin "1") (pinfunction "1_1") (pintype "passive"))
      (node (ref "SV1") (pin "2") (pinfunction "2_2") (pintype "passive"))
    )
    (net (code "56") (name "Net-(R5-Pad1)") (class "Default")
      (node (ref "R5") (pin "1") (pinfunction "1_1") (pintype "passive"))
      (node (ref "SJ1") (pin "2") (pinfunction "2_2") (pintype "passive"))
    )
    (net (code "57") (name "Net-(R6-Pad1)") (class "Default")
      (node (ref "R6") (pin "1") (pinfunction "1_1") (pintype "passive"))
      (node (ref "SJ2") (pin "2") (pinfunction "2_2") (pintype "passive"))
    )
    (net (code "58") (name "Net-(R7-Pad1)") (class "Default")
      (node (ref "R7") (pin "1") (pinfunction "1_1") (pintype "passive"))
      (node (ref "SJ3") (pin "2") (pinfunction "2_2") (pintype "passive"))
    )
    (net (code "59") (name "Net-(R8-Pad1)") (class "Default")
      (node (ref "R8") (pin "1") (pinfunction "1_1") (pintype "passive"))
      (node (ref "SJ4") (pin "2") (pinfunction "2_2") (pintype "passive"))
    )
    (net (code "60") (name "Net-(X2--1)") (class "Default")
      (node (ref "R34") (pin "1") (pinfunction "1_1") (pintype "passive"))
      (node (ref "X2") (pin "P1") (pinfunction "-1_P1") (pintype "bidirectional"))
    )
    (net (code "61") (name "Net-(X2--3)") (class "Default")
      (node (ref "R33") (pin "1") (pinfunction "1_1") (pintype "passive"))
      (node (ref "X2") (pin "P3") (pinfunction "-3_P3") (pintype "bidirectional"))
    )
    (net (code "62") (name "Net-(X5--1)") (class "Default")
      (node (ref "R44") (pin "2") (pinfunction "2_2") (pintype "passive"))
      (node (ref "X5") (pin "P1") (pinfunction "-1_P1") (pintype "bidirectional"))
    )
    (net (code "63") (name "Net-(X5--3)") (class "Default")
      (node (ref "R45") (pin "2") (pinfunction "2_2") (pintype "passive"))
      (node (ref "X5") (pin "P3") (pinfunction "-3_P3") (pintype "bidirectional"))
    )
  )
)
